# Qwiic_keypad.net
KiCad netlist of a schematic drawn in EAGLE
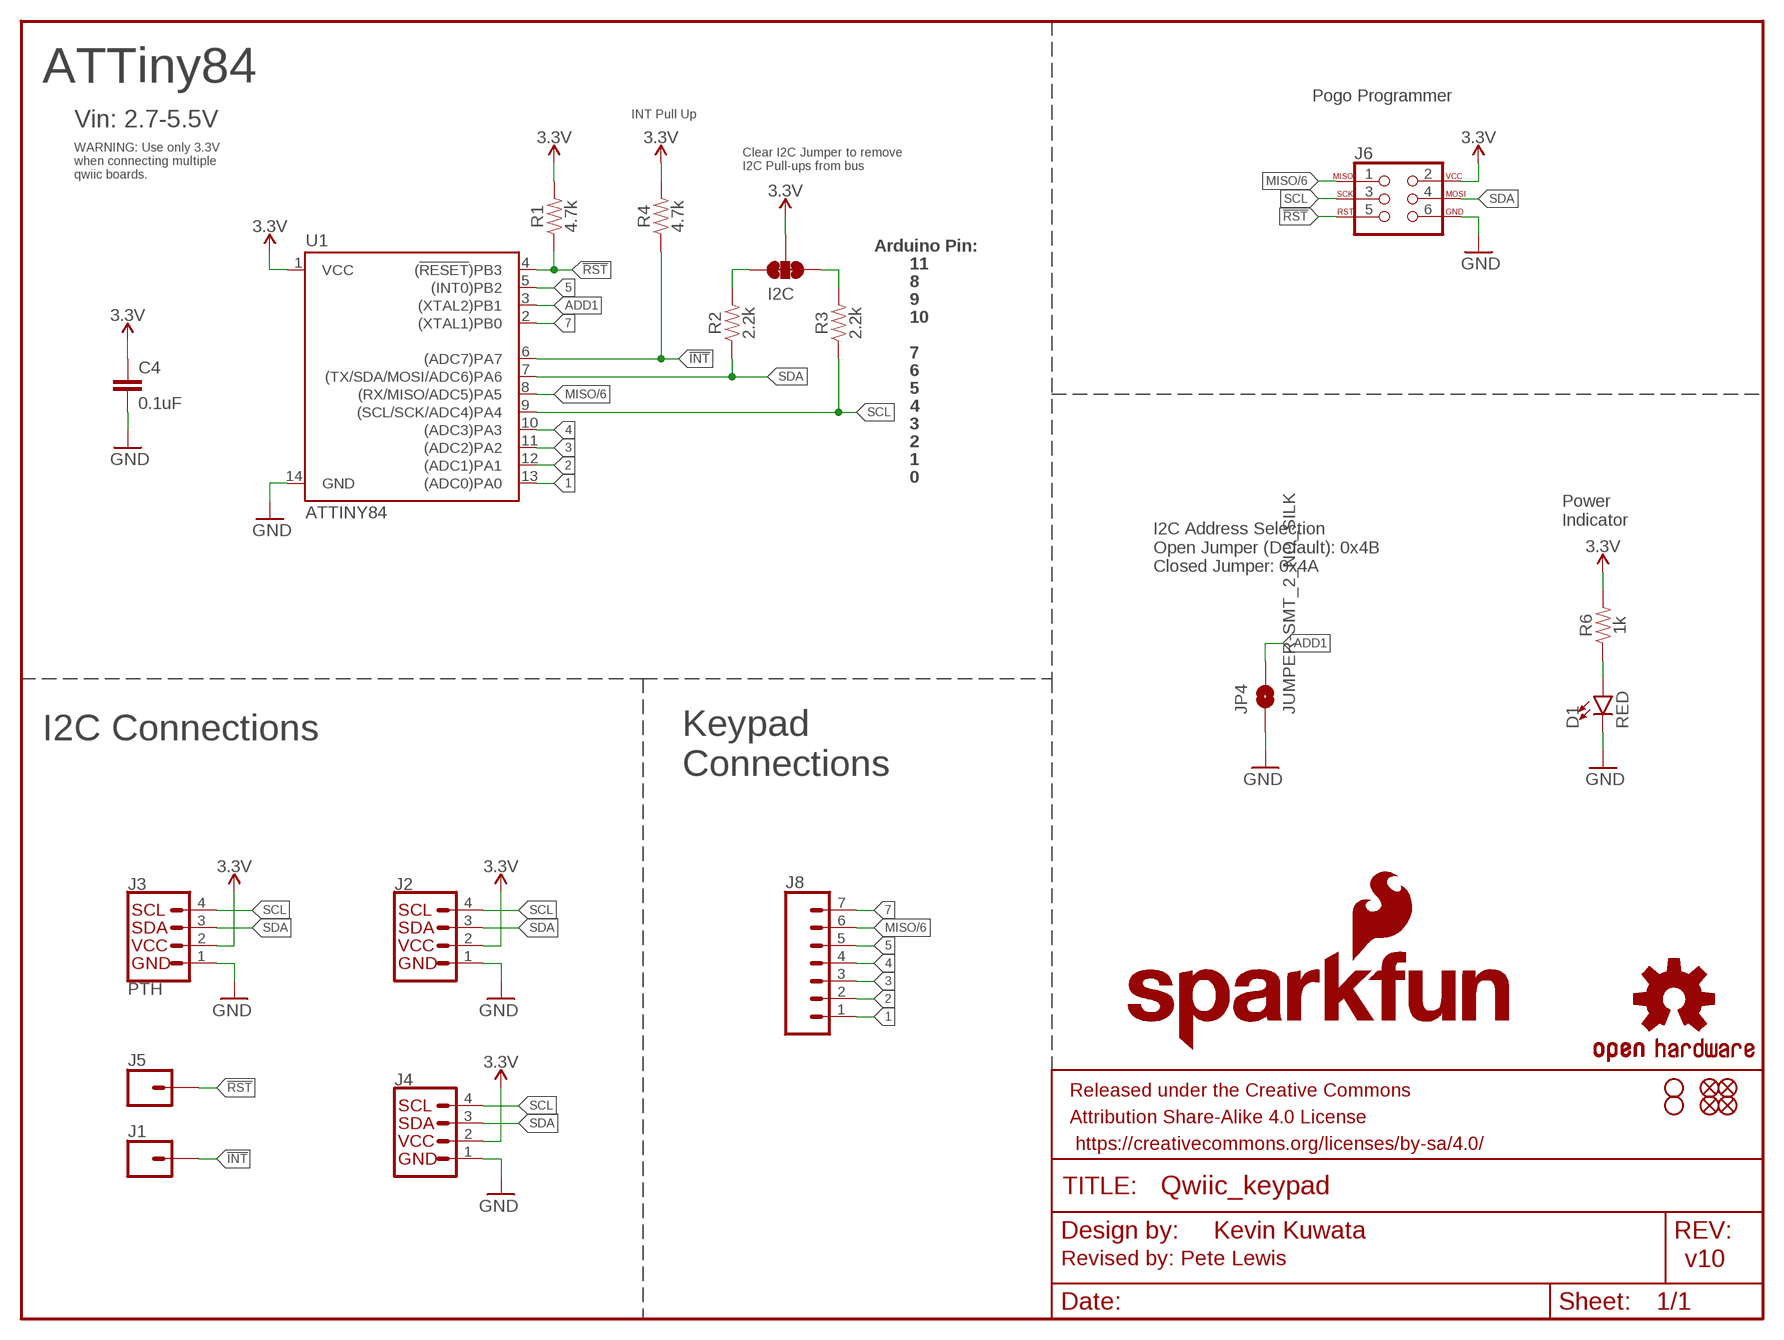
[diagram p0: schematic, sheet 1]

(export (version "E")
  (design (tool "Eeschema 10.0.6"))
  (components
    (comp (ref "C4")
      (value "0.1uF")
      (footprint "eagle-import:0603")
      (libsource (lib "eagle-import") (part "0.1UF-0603-25V-(+80/-20%)"))
    )
    (comp (ref "D1")
      (value "RED")
      (footprint "eagle-import:LED-0603")
      (libsource (lib "eagle-import") (part "LED-RED0603"))
    )
    (comp (ref "FRAME1")
      (value "FRAME-LETTER")
      (footprint "eagle-import:CREATIVE_COMMONS")
      (libsource (lib "eagle-import") (part "FRAME-LETTER"))
    )
    (comp (ref "H1")
      (value "STAND-OFF")
      (footprint "eagle-import:STAND-OFF")
      (libsource (lib "eagle-import") (part "STAND-OFF"))
    )
    (comp (ref "H2")
      (value "STAND-OFF")
      (footprint "eagle-import:STAND-OFF")
      (libsource (lib "eagle-import") (part "STAND-OFF"))
    )
    (comp (ref "I2C")
      (value "JUMPER-SMT_3_2-NC_TRACE_SILK")
      (footprint "eagle-import:SMT-JUMPER_3_2-NC_TRACE_SILK")
      (libsource (lib "eagle-import") (part "JUMPER-SMT_3_2-NC_TRACE_SILK"))
    )
    (comp (ref "J1")
      (value "CONN_01PTH_NO_SILK_YES_STOP")
      (footprint "eagle-import:1X01_NO_SILK")
      (libsource (lib "eagle-import") (part "CONN_01PTH_NO_SILK_YES_STOP"))
    )
    (comp (ref "J2")
      (value "QWIIC_CONNECTORJS-1MM")
      (footprint "eagle-import:JST04_1MM_RA")
      (libsource (lib "eagle-import") (part "QWIIC_CONNECTORJS-1MM"))
    )
    (comp (ref "J3")
      (value "PTH")
      (footprint "eagle-import:1X04_NO_SILK")
      (libsource (lib "eagle-import") (part "I2C_STANDARD_NO_SILK"))
    )
    (comp (ref "J4")
      (value "QWIIC_CONNECTORJS-1MM")
      (footprint "eagle-import:JST04_1MM_RA")
      (libsource (lib "eagle-import") (part "QWIIC_CONNECTORJS-1MM"))
    )
    (comp (ref "J5")
      (value "CONN_01PTH_NO_SILK_YES_STOP")
      (footprint "eagle-import:1X01_NO_SILK")
      (libsource (lib "eagle-import") (part "CONN_01PTH_NO_SILK_YES_STOP"))
    )
    (comp (ref "J6")
      (value "AVR_SPI_PROG_3X2TESTPOINTS")
      (footprint "eagle-import:2X3_TEST_POINTS")
      (libsource (lib "eagle-import") (part "AVR_SPI_PROG_3X2TESTPOINTS"))
    )
    (comp (ref "J8")
      (value "CONN_07LOCK_NO_SILK")
      (footprint "eagle-import:1X07_LOCK_NO_SILK")
      (libsource (lib "eagle-import") (part "CONN_07LOCK_NO_SILK"))
    )
    (comp (ref "JP1")
      (value "FIDUCIALUFIDUCIAL")
      (footprint "eagle-import:MICRO-FIDUCIAL")
      (libsource (lib "eagle-import") (part "FIDUCIALUFIDUCIAL"))
    )
    (comp (ref "JP2")
      (value "FIDUCIALUFIDUCIAL")
      (footprint "eagle-import:MICRO-FIDUCIAL")
      (libsource (lib "eagle-import") (part "FIDUCIALUFIDUCIAL"))
    )
    (comp (ref "JP3")
      (value "FIDUCIALUFIDUCIAL")
      (footprint "eagle-import:MICRO-FIDUCIAL")
      (libsource (lib "eagle-import") (part "FIDUCIALUFIDUCIAL"))
    )
    (comp (ref "JP4")
      (value "JUMPER-SMT_2_NO_SILK")
      (footprint "eagle-import:SMT-JUMPER_2_NO_SILK")
      (libsource (lib "eagle-import") (part "JUMPER-SMT_2_NO_SILK"))
    )
    (comp (ref "JP6")
      (value "FIDUCIALUFIDUCIAL")
      (footprint "eagle-import:MICRO-FIDUCIAL")
      (libsource (lib "eagle-import") (part "FIDUCIALUFIDUCIAL"))
    )
    (comp (ref "LOGO1")
      (value "OSHW-LOGOMINI")
      (footprint "eagle-import:OSHW-LOGO-MINI")
      (libsource (lib "eagle-import") (part "OSHW-LOGOMINI"))
    )
    (comp (ref "LOGO2")
      (value "SFE_LOGO_NAME_FLAME.1_INCH")
      (footprint "eagle-import:SFE_LOGO_NAME_FLAME_.1")
      (libsource (lib "eagle-import") (part "SFE_LOGO_NAME_FLAME.1_INCH"))
    )
    (comp (ref "LOGO3")
      (value "SFE_LOGO_FLAME.2_INCH")
      (footprint "eagle-import:SFE_LOGO_FLAME_.2")
      (libsource (lib "eagle-import") (part "SFE_LOGO_FLAME.2_INCH"))
    )
    (comp (ref "R1")
      (value "4.7k")
      (footprint "eagle-import:0603")
      (libsource (lib "eagle-import") (part "4.7KOHM-0603-1/10W-1%"))
    )
    (comp (ref "R2")
      (value "2.2k")
      (footprint "eagle-import:0603")
      (libsource (lib "eagle-import") (part "2.2KOHM-0603-1/10W-1%"))
    )
    (comp (ref "R3")
      (value "2.2k")
      (footprint "eagle-import:0603")
      (libsource (lib "eagle-import") (part "2.2KOHM-0603-1/10W-1%"))
    )
    (comp (ref "R4")
      (value "4.7k")
      (footprint "eagle-import:0603")
      (libsource (lib "eagle-import") (part "4.7KOHM-0603-1/10W-1%"))
    )
    (comp (ref "R6")
      (value "1k")
      (footprint "eagle-import:0603")
      (libsource (lib "eagle-import") (part "1KOHM-0603-1/10W-1%"))
    )
    (comp (ref "U1")
      (value "ATTINY84")
      (footprint "eagle-import:SO14")
      (libsource (lib "eagle-import") (part "ATTINY84"))
    )
  )
  (nets
    (net (code "1") (name "/~{INT}") (class "Default")
      (node (ref "J1") (pin "1") (pinfunction "1_1") (pintype "passive"))
      (node (ref "R4") (pin "1") (pinfunction "1_1") (pintype "passive"))
      (node (ref "U1") (pin "6") (pinfunction "(ADC7)PA7_6") (pintype "bidirectional"))
    )
    (net (code "2") (name "/~{RST}") (class "Default")
      (node (ref "J5") (pin "1") (pinfunction "1_1") (pintype "passive"))
      (node (ref "J6") (pin "5") (pinfunction "5_5") (pintype "passive"))
      (node (ref "R1") (pin "1") (pinfunction "1_1") (pintype "passive"))
      (node (ref "U1") (pin "4") (pinfunction "(~{RESET})PB3_4") (pintype "bidirectional"))
    )
    (net (code "3") (name "1") (class "Default")
      (node (ref "J8") (pin "1") (pinfunction "1_1") (pintype "passive"))
      (node (ref "U1") (pin "13") (pinfunction "(ADC0)PA0_13") (pintype "bidirectional"))
    )
    (net (code "4") (name "2") (class "Default")
      (node (ref "J8") (pin "2") (pinfunction "2_2") (pintype "passive"))
      (node (ref "U1") (pin "12") (pinfunction "(ADC1)PA1_12") (pintype "bidirectional"))
    )
    (net (code "5") (name "3") (class "Default")
      (node (ref "J8") (pin "3") (pinfunction "3_3") (pintype "passive"))
      (node (ref "U1") (pin "11") (pinfunction "(ADC2)PA2_11") (pintype "bidirectional"))
    )
    (net (code "6") (name "3.3V") (class "Default")
      (node (ref "C4") (pin "1") (pinfunction "1_1") (pintype "passive"))
      (node (ref "I2C") (pin "2") (pinfunction "2_2") (pintype "passive"))
      (node (ref "J2") (pin "2") (pinfunction "2_2") (pintype "power_in"))
      (node (ref "J3") (pin "2") (pinfunction "2_2") (pintype "power_in"))
      (node (ref "J4") (pin "2") (pinfunction "2_2") (pintype "power_in"))
      (node (ref "J6") (pin "2") (pinfunction "2_2") (pintype "passive"))
      (node (ref "R1") (pin "2") (pinfunction "2_2") (pintype "passive"))
      (node (ref "R4") (pin "2") (pinfunction "2_2") (pintype "passive"))
      (node (ref "R6") (pin "2") (pinfunction "2_2") (pintype "passive"))
      (node (ref "U1") (pin "1") (pinfunction "VCC_1") (pintype "bidirectional"))
    )
    (net (code "7") (name "4") (class "Default")
      (node (ref "J8") (pin "4") (pinfunction "4_4") (pintype "passive"))
      (node (ref "U1") (pin "10") (pinfunction "(ADC3)PA3_10") (pintype "bidirectional"))
    )
    (net (code "8") (name "5") (class "Default")
      (node (ref "J8") (pin "5") (pinfunction "5_5") (pintype "passive"))
      (node (ref "U1") (pin "5") (pinfunction "(INT0)PB2_5") (pintype "bidirectional"))
    )
    (net (code "9") (name "7") (class "Default")
      (node (ref "J8") (pin "7") (pinfunction "7_7") (pintype "passive"))
      (node (ref "U1") (pin "2") (pinfunction "(XTAL1)PB0_2") (pintype "bidirectional"))
    )
    (net (code "10") (name "ADD1") (class "Default")
      (node (ref "JP4") (pin "2") (pinfunction "2_2") (pintype "passive"))
      (node (ref "U1") (pin "3") (pinfunction "(XTAL2)PB1_3") (pintype "bidirectional"))
    )
    (net (code "11") (name "GND") (class "Default")
      (node (ref "C4") (pin "2") (pinfunction "2_2") (pintype "passive"))
      (node (ref "D1") (pin "C") (pinfunction "C_C") (pintype "passive"))
      (node (ref "J2") (pin "1") (pinfunction "1_1") (pintype "power_in"))
      (node (ref "J3") (pin "1") (pinfunction "1_1") (pintype "power_in"))
      (node (ref "J4") (pin "1") (pinfunction "1_1") (pintype "power_in"))
      (node (ref "J6") (pin "6") (pinfunction "6_6") (pintype "passive"))
      (node (ref "JP4") (pin "1") (pinfunction "1_1") (pintype "passive"))
      (node (ref "U1") (pin "14") (pinfunction "GND_14") (pintype "bidirectional"))
    )
    (net (code "12") (name "MISO{slash}6") (class "Default")
      (node (ref "J6") (pin "1") (pinfunction "1_1") (pintype "passive"))
      (node (ref "J8") (pin "6") (pinfunction "6_6") (pintype "passive"))
      (node (ref "U1") (pin "8") (pinfunction "(RX/MISO/ADC5)PA5_8") (pintype "bidirectional"))
    )
    (net (code "13") (name "Net-(D1-PadA)") (class "Default")
      (node (ref "D1") (pin "A") (pinfunction "A_A") (pintype "passive"))
      (node (ref "R6") (pin "1") (pinfunction "1_1") (pintype "passive"))
    )
    (net (code "14") (name "Net-(I2C-Pad1)") (class "Default")
      (node (ref "I2C") (pin "1") (pinfunction "1_1") (pintype "passive"))
      (node (ref "R3") (pin "2") (pinfunction "2_2") (pintype "passive"))
    )
    (net (code "15") (name "Net-(I2C-Pad3)") (class "Default")
      (node (ref "I2C") (pin "3") (pinfunction "3_3") (pintype "passive"))
      (node (ref "R2") (pin "2") (pinfunction "2_2") (pintype "passive"))
    )
    (net (code "16") (name "SCL") (class "Default")
      (node (ref "J2") (pin "4") (pinfunction "4_4") (pintype "passive"))
      (node (ref "J3") (pin "4") (pinfunction "4_4") (pintype "passive"))
      (node (ref "J4") (pin "4") (pinfunction "4_4") (pintype "passive"))
      (node (ref "J6") (pin "3") (pinfunction "3_3") (pintype "passive"))
      (node (ref "R3") (pin "1") (pinfunction "1_1") (pintype "passive"))
      (node (ref "U1") (pin "9") (pinfunction "(SCL/SCK/ADC4)PA4_9") (pintype "bidirectional"))
    )
    (net (code "17") (name "SDA") (class "Default")
      (node (ref "J2") (pin "3") (pinfunction "3_3") (pintype "passive"))
      (node (ref "J3") (pin "3") (pinfunction "3_3") (pintype "passive"))
      (node (ref "J4") (pin "3") (pinfunction "3_3") (pintype "passive"))
      (node (ref "J6") (pin "4") (pinfunction "4_4") (pintype "passive"))
      (node (ref "R2") (pin "1") (pinfunction "1_1") (pintype "passive"))
      (node (ref "U1") (pin "7") (pinfunction "(TX/SDA/MOSI/ADC6)PA6_7") (pintype "bidirectional"))
    )
  )
)
